# Sheet1.net
KiCad netlist of a schematic drawn in Altium Designer
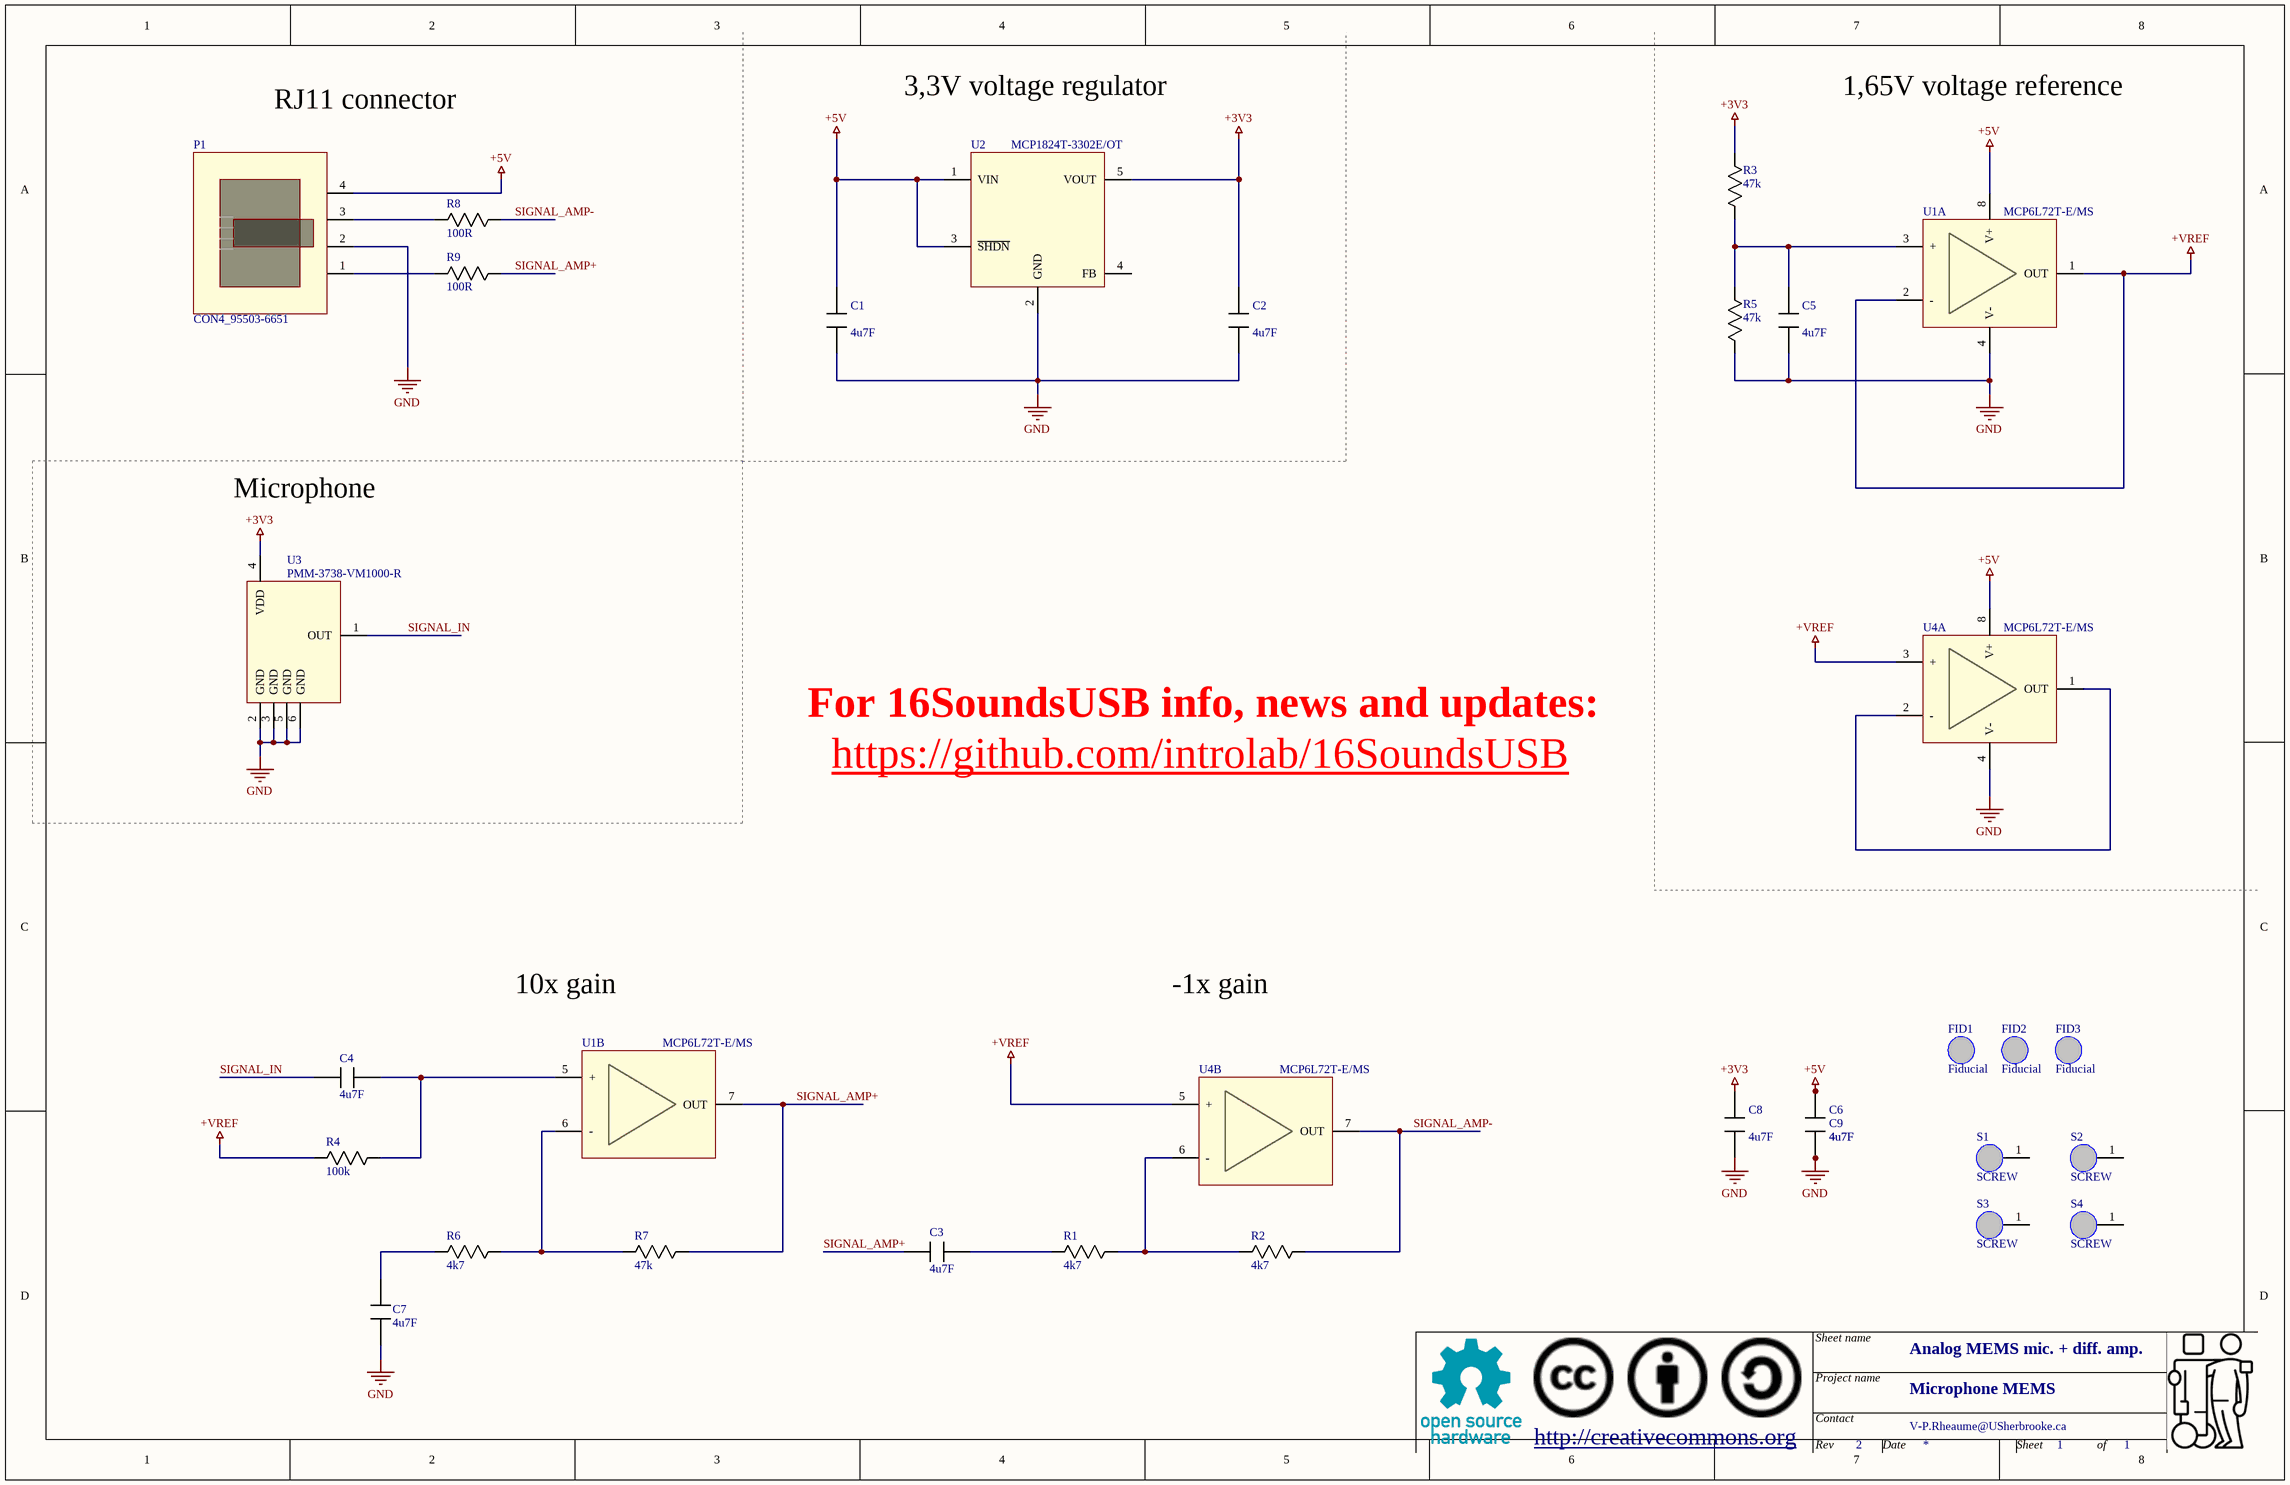
[diagram p0: Sheet1.SchDoc]

(export (version "E")
  (design (tool "Eeschema 10.0.6"))
  (components
    (comp (ref "C1")
      (value "4u7F")
      (footprint "0402")
      (description "Capacitor")
      (fields (field (name "MFG") "Samsung"))
      (libsource (lib "INTER_2014") (part "Capacitor"))
    )
    (comp (ref "C2")
      (value "4u7F")
      (footprint "0402")
      (description "Capacitor")
      (fields (field (name "MFG") "Samsung"))
      (libsource (lib "INTER_2014") (part "Capacitor"))
    )
    (comp (ref "C3")
      (value "4u7F")
      (footprint "0402")
      (description "Capacitor")
      (fields (field (name "MFG") "Samsung"))
      (libsource (lib "INTER_2014") (part "Capacitor"))
    )
    (comp (ref "C4")
      (value "4u7F")
      (footprint "0402")
      (description "Capacitor")
      (fields (field (name "MFG") "Samsung"))
      (libsource (lib "INTER_2014") (part "Capacitor"))
    )
    (comp (ref "C5")
      (value "4u7F")
      (footprint "0402")
      (description "Capacitor")
      (fields (field (name "MFG") "Samsung"))
      (libsource (lib "INTER_2014") (part "Capacitor"))
    )
    (comp (ref "C6")
      (value "4u7F")
      (footprint "0402")
      (description "Capacitor")
      (fields (field (name "MFG") "Samsung"))
      (libsource (lib "INTER_2014") (part "Capacitor"))
    )
    (comp (ref "C7")
      (value "4u7F")
      (footprint "0402")
      (description "Capacitor")
      (fields (field (name "MFG") "Samsung"))
      (libsource (lib "INTER_2014") (part "Capacitor"))
    )
    (comp (ref "C8")
      (value "4u7F")
      (footprint "0402")
      (description "Capacitor")
      (fields (field (name "MFG") "Samsung"))
      (libsource (lib "INTER_2014") (part "Capacitor"))
    )
    (comp (ref "C9")
      (value "4u7F")
      (footprint "0402")
      (description "Capacitor")
      (fields (field (name "MFG") "Samsung"))
      (libsource (lib "INTER_2014") (part "Capacitor"))
    )
    (comp (ref "FID1") (value "Fiducial") (footprint "FIDUCIAL") (libsource (lib "lib") (part "Fiducial")))
    (comp (ref "FID2") (value "Fiducial") (footprint "FIDUCIAL") (libsource (lib "lib") (part "Fiducial")))
    (comp (ref "FID3") (value "Fiducial") (footprint "FIDUCIAL") (libsource (lib "lib") (part "Fiducial")))
    (comp (ref "P1")
      (value "CON4_95503-6651")
      (footprint "CONN_RJ11_SMT_VERTICAL")
      (description "4p4c RJ11")
      (fields (field (name "MFG") "Molex"))
      (libsource (lib "INTER_2014") (part "CON4_95503-6651"))
    )
    (comp (ref "R1")
      (value "4k7")
      (footprint "0402")
      (description "Resistor")
      (fields (field (name "MFG") "Yageo"))
      (libsource (lib "INTER_2014") (part "Resistor"))
    )
    (comp (ref "R2")
      (value "4k7")
      (footprint "0402")
      (description "Resistor")
      (fields (field (name "MFG") "Yageo"))
      (libsource (lib "INTER_2014") (part "Resistor"))
    )
    (comp (ref "R3")
      (value "47k")
      (footprint "0402")
      (description "Resistor")
      (fields (field (name "MFG") "Yageo"))
      (libsource (lib "INTER_2014") (part "Resistor"))
    )
    (comp (ref "R4")
      (value "100k")
      (footprint "0402")
      (description "Resistor")
      (fields (field (name "MFG") "Yageo"))
      (libsource (lib "INTER_2014") (part "Resistor"))
    )
    (comp (ref "R5")
      (value "47k")
      (footprint "0402")
      (description "Resistor")
      (fields (field (name "MFG") "Yageo"))
      (libsource (lib "INTER_2014") (part "Resistor"))
    )
    (comp (ref "R6")
      (value "4k7")
      (footprint "0402")
      (description "Resistor")
      (fields (field (name "MFG") "Yageo"))
      (libsource (lib "INTER_2014") (part "Resistor"))
    )
    (comp (ref "R7")
      (value "47k")
      (footprint "0402")
      (description "Resistor")
      (fields (field (name "MFG") "Yageo"))
      (libsource (lib "INTER_2014") (part "Resistor"))
    )
    (comp (ref "R8")
      (value "100R")
      (footprint "0402")
      (description "Resistor")
      (fields (field (name "MFG") "Samsung"))
      (libsource (lib "INTER_2014") (part "Resistor"))
    )
    (comp (ref "R9")
      (value "100R")
      (footprint "0402")
      (description "Resistor")
      (fields (field (name "MFG") "Samsung"))
      (libsource (lib "INTER_2014") (part "Resistor"))
    )
    (comp (ref "S1")
      (value "SCREW")
      (footprint "SCREW_M2.5")
      (description "Screw hole")
      (libsource (lib "INTER_2014") (part "SCREW"))
    )
    (comp (ref "S2")
      (value "SCREW")
      (footprint "SCREW_M2.5")
      (description "Screw hole")
      (libsource (lib "INTER_2014") (part "SCREW"))
    )
    (comp (ref "S3")
      (value "SCREW")
      (footprint "SCREW_M2.5")
      (description "Screw hole")
      (libsource (lib "INTER_2014") (part "SCREW"))
    )
    (comp (ref "S4")
      (value "SCREW")
      (footprint "SCREW_M2.5")
      (description "Screw hole")
      (libsource (lib "INTER_2014") (part "SCREW"))
    )
    (comp (ref "U1")
      (value "OPA_DUAL")
      (footprint "SOP127P600-8N")
      (description "Dual amplifier (standard)")
      (fields (field (name "MFG") "Microchip") (field (name "MFG_PN") "MCP6L72T-E/MS"))
      (libsource (lib "INTER_2014") (part "OPA_DUAL"))
    )
    (comp (ref "U2")
      (value "MCP1824")
      (footprint "SOT23_5")
      (description "Adjustable linear voltage regulator")
      (fields (field (name "MFG") "Microchip") (field (name "MFG_PN") "MCP1824T-3302E/OT"))
      (libsource (lib "INTER_2014") (part "MCP1824"))
    )
    (comp (ref "U3")
      (value "VM1000-R")
      (footprint "PMM-3738-VM1000-R")
      (description "MIC PIEZO MEMS ANLG OMNI -38DB bottom port")
      (fields (field (name "MFG") "Vesper") (field (name "MFG_PN") "PMM-3738-VM1000-R"))
      (libsource (lib "INTER_2014") (part "VM1000-R"))
    )
    (comp (ref "U4")
      (value "OPA_DUAL")
      (footprint "SOP127P600-8N")
      (description "Dual amplifier (standard)")
      (fields (field (name "MFG") "Microchip") (field (name "MFG_PN") "MCP6L72T-E/MS"))
      (libsource (lib "INTER_2014") (part "OPA_DUAL"))
    )
  )
  (nets
    (net (code "1") (name "+3V3") (class "Default")
      (node (ref "C2") (pin "1") (pintype "passive"))
      (node (ref "C8") (pin "1") (pintype "passive"))
      (node (ref "R3") (pin "2") (pintype "passive"))
      (node (ref "U2") (pin "5") (pinfunction "VOUT_5") (pintype "passive"))
      (node (ref "U3") (pin "4") (pinfunction "VDD_4") (pintype "passive"))
    )
    (net (code "2") (name "+5V") (class "Default")
      (node (ref "C1") (pin "1") (pintype "passive"))
      (node (ref "C6") (pin "1") (pintype "passive"))
      (node (ref "C9") (pin "1") (pintype "passive"))
      (node (ref "P1") (pin "4") (pintype "passive"))
      (node (ref "U1") (pin "8") (pinfunction "V+_8") (pintype "passive"))
      (node (ref "U2") (pin "1") (pinfunction "VIN_1") (pintype "passive"))
      (node (ref "U2") (pin "3") (pinfunction "~{SHDN}_3") (pintype "passive"))
      (node (ref "U4") (pin "8") (pinfunction "V+_8") (pintype "passive"))
    )
    (net (code "3") (name "+VREF") (class "Default")
      (node (ref "R4") (pin "2") (pintype "passive"))
      (node (ref "U1") (pin "1") (pinfunction "OUT_1") (pintype "passive"))
      (node (ref "U1") (pin "2") (pinfunction "-_2") (pintype "passive"))
      (node (ref "U4") (pin "3") (pinfunction "+_3") (pintype "passive"))
      (node (ref "U4") (pin "5") (pinfunction "+_5") (pintype "passive"))
    )
    (net (code "4") (name "/SIGNAL_AMP+") (class "Default")
      (node (ref "C3") (pin "2") (pintype "passive"))
      (node (ref "R7") (pin "1") (pintype "passive"))
      (node (ref "R9") (pin "1") (pintype "passive"))
      (node (ref "U1") (pin "7") (pinfunction "OUT_7") (pintype "passive"))
    )
    (net (code "5") (name "/SIGNAL_AMP-") (class "Default")
      (node (ref "R2") (pin "1") (pintype "passive"))
      (node (ref "R8") (pin "1") (pintype "passive"))
      (node (ref "U4") (pin "7") (pinfunction "OUT_7") (pintype "passive"))
    )
    (net (code "6") (name "/SIGNAL_IN") (class "Default")
      (node (ref "C4") (pin "1") (pintype "passive"))
      (node (ref "U3") (pin "1") (pinfunction "OUT_1") (pintype "passive"))
    )
    (net (code "7") (name "GND") (class "Default")
      (node (ref "C1") (pin "2") (pintype "passive"))
      (node (ref "C2") (pin "2") (pintype "passive"))
      (node (ref "C5") (pin "2") (pintype "passive"))
      (node (ref "C6") (pin "2") (pintype "passive"))
      (node (ref "C7") (pin "1") (pintype "passive"))
      (node (ref "C8") (pin "2") (pintype "passive"))
      (node (ref "C9") (pin "2") (pintype "passive"))
      (node (ref "P1") (pin "2") (pintype "passive"))
      (node (ref "R5") (pin "1") (pintype "passive"))
      (node (ref "U1") (pin "4") (pinfunction "V-_4") (pintype "passive"))
      (node (ref "U2") (pin "2") (pinfunction "GND_2") (pintype "passive"))
      (node (ref "U3") (pin "2") (pinfunction "GND_2") (pintype "passive"))
      (node (ref "U3") (pin "3") (pinfunction "GND_3") (pintype "passive"))
      (node (ref "U3") (pin "5") (pinfunction "GND_5") (pintype "passive"))
      (node (ref "U3") (pin "6") (pinfunction "GND_6") (pintype "passive"))
      (node (ref "U4") (pin "4") (pinfunction "V-_4") (pintype "passive"))
    )
    (net (code "8") (name "Net-(C3-Pad1)") (class "Default")
      (node (ref "C3") (pin "1") (pintype "passive"))
      (node (ref "R1") (pin "2") (pintype "passive"))
    )
    (net (code "9") (name "Net-(C7-Pad2)") (class "Default")
      (node (ref "C7") (pin "2") (pintype "passive"))
      (node (ref "R6") (pin "2") (pintype "passive"))
    )
    (net (code "10") (name "Net-(P1-Pad1)") (class "Default")
      (node (ref "P1") (pin "1") (pintype "passive"))
      (node (ref "R9") (pin "2") (pintype "passive"))
    )
    (net (code "11") (name "Net-(P1-Pad3)") (class "Default")
      (node (ref "P1") (pin "3") (pintype "passive"))
      (node (ref "R8") (pin "2") (pintype "passive"))
    )
    (net (code "12") (name "Net-(U1A-+)") (class "Default")
      (node (ref "C5") (pin "1") (pintype "passive"))
      (node (ref "R3") (pin "1") (pintype "passive"))
      (node (ref "R5") (pin "2") (pintype "passive"))
      (node (ref "U1") (pin "3") (pinfunction "+_3") (pintype "passive"))
    )
    (net (code "13") (name "Net-(U1B-+)") (class "Default")
      (node (ref "C4") (pin "2") (pintype "passive"))
      (node (ref "R4") (pin "1") (pintype "passive"))
      (node (ref "U1") (pin "5") (pinfunction "+_5") (pintype "passive"))
    )
    (net (code "14") (name "Net-(U1B--)") (class "Default")
      (node (ref "R6") (pin "1") (pintype "passive"))
      (node (ref "R7") (pin "2") (pintype "passive"))
      (node (ref "U1") (pin "6") (pinfunction "-_6") (pintype "passive"))
    )
    (net (code "15") (name "Net-(U4A--)") (class "Default")
      (node (ref "U4") (pin "1") (pinfunction "OUT_1") (pintype "passive"))
      (node (ref "U4") (pin "2") (pinfunction "-_2") (pintype "passive"))
    )
    (net (code "16") (name "Net-(U4B--)") (class "Default")
      (node (ref "R1") (pin "1") (pintype "passive"))
      (node (ref "R2") (pin "2") (pintype "passive"))
      (node (ref "U4") (pin "6") (pinfunction "-_6") (pintype "passive"))
    )
    (net (code "17") (name "unconnected-(FID1-Pad0)") (class "Default")
      (node (ref "FID1") (pin "0") (pintype "passive"))
    )
    (net (code "18") (name "unconnected-(FID2-Pad0)") (class "Default")
      (node (ref "FID2") (pin "0") (pintype "passive"))
    )
    (net (code "19") (name "unconnected-(FID3-Pad0)") (class "Default")
      (node (ref "FID3") (pin "0") (pintype "passive"))
    )
    (net (code "20") (name "unconnected-(S1-Pad1)") (class "Default")
      (node (ref "S1") (pin "1") (pintype "passive"))
    )
    (net (code "21") (name "unconnected-(S2-Pad1)") (class "Default")
      (node (ref "S2") (pin "1") (pintype "passive"))
    )
    (net (code "22") (name "unconnected-(S3-Pad1)") (class "Default")
      (node (ref "S3") (pin "1") (pintype "passive"))
    )
    (net (code "23") (name "unconnected-(S4-Pad1)") (class "Default")
      (node (ref "S4") (pin "1") (pintype "passive"))
    )
    (net (code "24") (name "unconnected-(U2-FB-Pad4)") (class "Default")
      (node (ref "U2") (pin "4") (pinfunction "FB_4") (pintype "passive"))
    )
  )
)
